# Sensor.net
KiCad netlist of a schematic drawn in Altium Designer
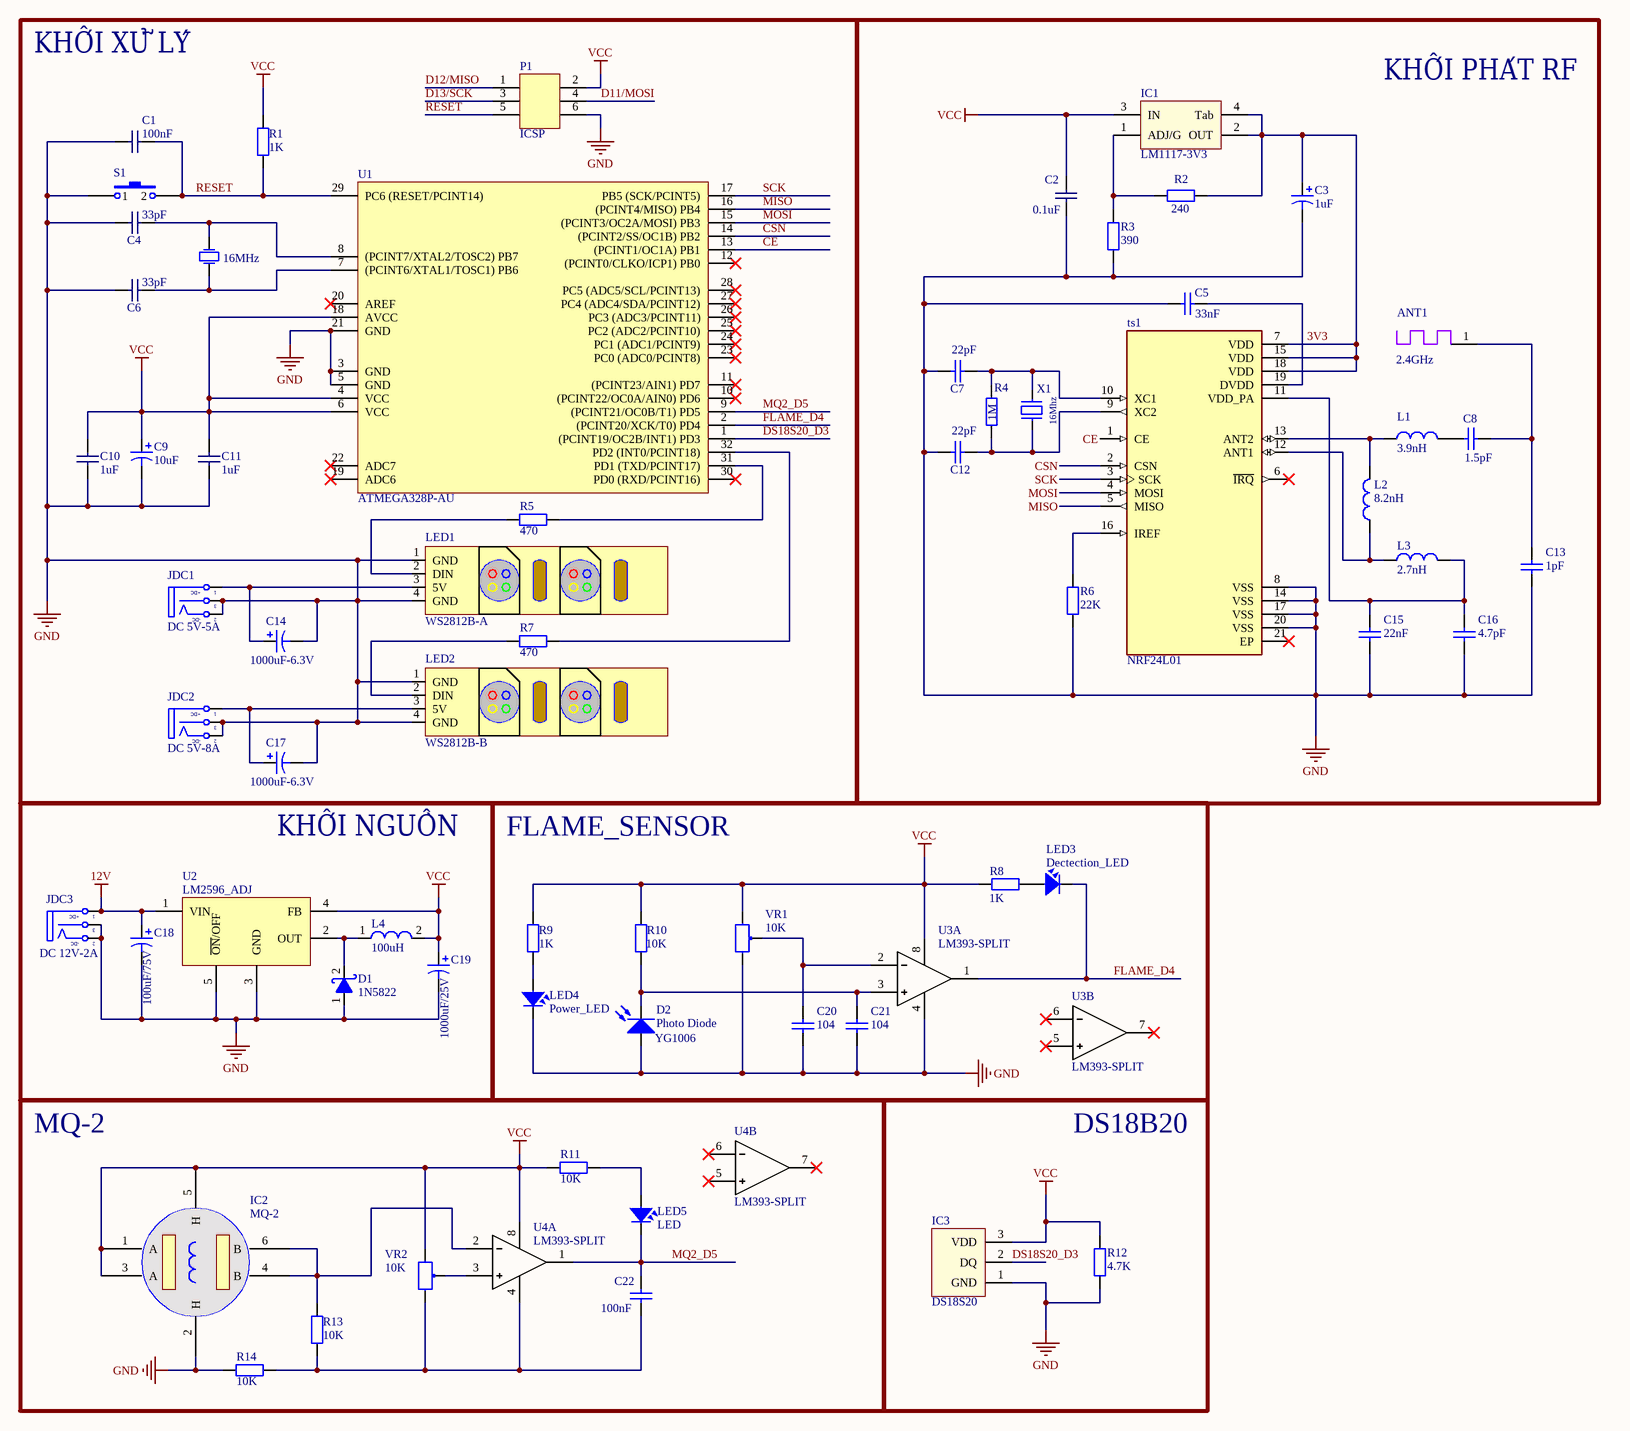
[diagram p0: Sensor.SchDoc]

(export (version "E")
  (design (tool "Eeschema 10.0.6"))
  (components
    (comp (ref "ANT1")
      (value "2.4GHz")
      (footprint "PATCH ANTEN 2.45GHZ")
      (description "PCB ANTENNA 2.45GHZ")
      (libsource (lib "BYTECH_HW_LIB_2019 (1)") (part "PCB antenna 2.45GHZ"))
    )
    (comp (ref "C1")
      (value "100nF")
      (footprint "thuvien_altium:CAP0603")
      (description "capacitor non polar")
      (libsource (lib "thuvien_altium") (part "capacitor_non_polar"))
    )
    (comp (ref "C2")
      (value "0.1uF")
      (footprint "thuvien_altium:CAPC0805")
      (description "capacitor non polar")
      (libsource (lib "thuvien_altium") (part "capacitor_non_polar"))
    )
    (comp (ref "C3")
      (value "1uF")
      (footprint "CAP_0805")
      (description "Polarized Capacitor (Axial)")
      (fields (field (name "PUBLISHER") "Altium Limited"))
      (libsource (lib "My Library") (part "Cap Pol 5mm"))
    )
    (comp (ref "C4")
      (value "33pF")
      (footprint "thuvien_altium:CAP0603")
      (description "capacitor non polar")
      (libsource (lib "thuvien_altium") (part "capacitor_non_polar"))
    )
    (comp (ref "C5")
      (value "33nF")
      (footprint "CAPC0805")
      (description "Capacitor")
      (fields (field (name "PUBLISHER") "Altium Limited"))
      (libsource (lib "My Library") (part "CapCeramic"))
    )
    (comp (ref "C6")
      (value "33pF")
      (footprint "thuvien_altium:CAP0603")
      (description "capacitor non polar")
      (libsource (lib "thuvien_altium") (part "capacitor_non_polar"))
    )
    (comp (ref "C7")
      (value "22pF")
      (footprint "CAPC0805")
      (description "Capacitor")
      (fields (field (name "PUBLISHER") "Altium Limited"))
      (libsource (lib "My Library") (part "CapCeramic"))
    )
    (comp (ref "C8")
      (value "1.5pF")
      (footprint "CAPC0805")
      (description "Capacitor")
      (fields (field (name "PUBLISHER") "Altium Limited"))
      (libsource (lib "My Library") (part "CapCeramic"))
    )
    (comp (ref "C9")
      (value "10uF")
      (footprint "thuvien_altium:CAP1206_TANTALUM_YELLOW")
      (description "CAP TANT 10UF 16V 10% 1206")
      (fields (field (name "TOLERANCE") "±10%"))
      (libsource (lib "thuvien_altium") (part "T491A106K016AT"))
    )
    (comp (ref "C10")
      (value "1uF")
      (footprint "thuvien_altium:CAP0603")
      (description "capacitor non polar")
      (libsource (lib "thuvien_altium") (part "capacitor_non_polar"))
    )
    (comp (ref "C11")
      (value "1uF")
      (footprint "thuvien_altium:CAP0603")
      (description "capacitor non polar")
      (libsource (lib "thuvien_altium") (part "capacitor_non_polar"))
    )
    (comp (ref "C12")
      (value "22pF")
      (footprint "CAPC0805")
      (description "Capacitor")
      (fields (field (name "PUBLISHER") "Altium Limited"))
      (libsource (lib "My Library") (part "CapCeramic"))
    )
    (comp (ref "C13")
      (value "1pF")
      (footprint "CAPC0805")
      (description "Capacitor")
      (fields (field (name "PUBLISHER") "Altium Limited"))
      (libsource (lib "My Library") (part "CapCeramic"))
    )
    (comp (ref "C14")
      (value "1000uF-6.3V")
      (footprint "CAP-ALU-SMD-J")
      (description "Polarized Capacitor (Axial)")
      (fields (field (name "PUBLISHER") "Altium Limited"))
      (libsource (lib "My Library") (part "Cap Pol 5mm"))
    )
    (comp (ref "C15")
      (value "22nF")
      (footprint "CAPC0805")
      (description "Capacitor")
      (fields (field (name "PUBLISHER") "Altium Limited"))
      (libsource (lib "My Library") (part "CapCeramic"))
    )
    (comp (ref "C16")
      (value "4.7pF")
      (footprint "CAPC0805")
      (description "Capacitor")
      (fields (field (name "PUBLISHER") "Altium Limited"))
      (libsource (lib "My Library") (part "CapCeramic"))
    )
    (comp (ref "C17")
      (value "1000uF-6.3V")
      (footprint "CAP-ALU-SMD-J")
      (description "Polarized Capacitor (Axial)")
      (fields (field (name "PUBLISHER") "Altium Limited"))
      (libsource (lib "My Library") (part "Cap Pol 5mm"))
    )
    (comp (ref "C18")
      (value "100uF/75V")
      (footprint "C5mm")
      (description "Polarized Capacitor (Axial)")
      (fields (field (name "PUBLISHER") "Altium Limited"))
      (libsource (lib "My Library") (part "Cap Pol 5mm"))
    )
    (comp (ref "C19")
      (value "1000uF/25V")
      (footprint "C5mm")
      (description "Polarized Capacitor (Axial)")
      (fields (field (name "PUBLISHER") "Altium Limited"))
      (libsource (lib "My Library") (part "Cap Pol 5mm"))
    )
    (comp (ref "C20")
      (value "104")
      (footprint "C0805")
      (description "Capacitor")
      (fields (field (name "PUBLISHER") "Altium Limited"))
      (libsource (lib "My Library") (part "CapSMD"))
    )
    (comp (ref "C21")
      (value "104")
      (footprint "C0805")
      (description "Capacitor")
      (fields (field (name "PUBLISHER") "Altium Limited"))
      (libsource (lib "My Library") (part "CapSMD"))
    )
    (comp (ref "C22")
      (value "100nF")
      (footprint "CAP_0805")
      (description "Capacitor")
      (fields (field (name "PUBLISHER") "Altium Limited"))
      (libsource (lib "My Library") (part "CapCeramic"))
    )
    (comp (ref "D1")
      (value "1N5822")
      (footprint "DIOAD3070W130L950D530")
      (description "Schottky Rectifiers")
      (libsource (lib "My Library") (part "1N5822"))
    )
    (comp (ref "D2")
      (value "Photo Diode")
      (footprint "LED-5 GRe")
      (description "Photosensitive Diode")
      (fields (field (name "YG1006") "YG1006"))
      (libsource (lib "My Library") (part "Photo Diode"))
    )
    (comp (ref "IC1")
      (value "LM1117-3V3")
      (footprint "SOT223-4N")
      (description "3v3")
      (libsource (lib "[Devzone.vn]_SchLibrary") (part "LM1117_1"))
    )
    (comp (ref "IC2")
      (value "MQ-2")
      (footprint "MQ-2")
      (description "MQ-2 GAS SENSOR")
      (libsource (lib "My Library") (part "MQ-2"))
    )
    (comp (ref "IC3")
      (value "DS18S20")
      (footprint "JP3-C1T")
      (description "High Precision  1-Wire® Digital Thermometer")
      (libsource (lib "TechMT.VN_Lib_Project v2") (part "DS18S20"))
    )
    (comp (ref "JDC1")
      (value "DC 5V-5A")
      (footprint "DC-IN")
      (description "Jac DC input")
      (libsource (lib "[Devzone.vn]_SchLibrary") (part "DCIN"))
    )
    (comp (ref "JDC2")
      (value "DC 5V-8A")
      (footprint "DC-IN")
      (description "Jac DC input")
      (libsource (lib "[Devzone.vn]_SchLibrary") (part "DCIN"))
    )
    (comp (ref "JDC3")
      (value "DC 12V-2A")
      (footprint "DC-IN")
      (description "Jac DC input")
      (libsource (lib "[Devzone.vn]_SchLibrary") (part "DCIN"))
    )
    (comp (ref "L1")
      (value "3.9nH")
      (footprint "INDC_DR127-1")
      (description "Inductor")
      (libsource (lib "My Library") (part "L1"))
    )
    (comp (ref "L2")
      (value "8.2nH")
      (footprint "INDC_DR127-1")
      (description "Inductor")
      (libsource (lib "My Library") (part "L1"))
    )
    (comp (ref "L3")
      (value "2.7nH")
      (footprint "INDC_DR127-1")
      (description "Inductor")
      (libsource (lib "My Library") (part "L1"))
    )
    (comp (ref "L4")
      (value "100uH")
      (footprint "Inductor_SMD")
      (description "Inductor")
      (libsource (lib "My Library") (part "Inductor"))
    )
    (comp (ref "LED1")
      (value "WS2812B-A")
      (footprint "WS2812B")
      (description "WS2812B")
      (libsource (lib "CamBien") (part "WS2812B"))
    )
    (comp (ref "LED2")
      (value "WS2812B-B")
      (footprint "WS2812B")
      (description "WS2812B")
      (libsource (lib "CamBien") (part "WS2812B"))
    )
    (comp (ref "LED3")
      (value "Dectection_LED")
      (footprint "LED-0805-Blue")
      (libsource (lib "My Library") (part "LED SMD"))
    )
    (comp (ref "LED4")
      (value "Power_LED")
      (footprint "LED-0805-Red")
      (libsource (lib "My Library") (part "LED SMD"))
    )
    (comp (ref "LED5")
      (value "LED")
      (footprint "LED-0805-Red")
      (description "LED Single colour Green and Red")
      (libsource (lib "My Library") (part "LED"))
    )
    (comp (ref "P1")
      (value "ICSP")
      (footprint "thuvien_altium:HDR_M_2X3_2.54")
      (libsource (lib "thuvien_altium") (part "header_2x3pins"))
    )
    (comp (ref "R1")
      (value "1K")
      (footprint "DIEN TRO 0805")
      (description "Resistor SMD 0805")
      (fields (field (name "PUBLISHER") "Altium Limited"))
      (libsource (lib "") (part "R0805_1"))
    )
    (comp (ref "R2")
      (value "240")
      (footprint "RES_SMD_0805")
      (description "Resistor 1/4W")
      (libsource (lib "My Library") (part "R1/4W"))
    )
    (comp (ref "R3")
      (value "390")
      (footprint "RES_SMD_0805")
      (description "Resistor 1/4W")
      (libsource (lib "My Library") (part "R1/4W"))
    )
    (comp (ref "R4")
      (value "1M")
      (footprint "RES_SMD_0805")
      (description "Resistor 1/4W")
      (libsource (lib "My Library") (part "R1/4W"))
    )
    (comp (ref "R5")
      (value "470")
      (footprint "DIEN TRO 0805")
      (description "Resistor SMD 0805")
      (fields (field (name "PUBLISHER") "Altium Limited"))
      (libsource (lib "My Library") (part "R0805"))
    )
    (comp (ref "R6")
      (value "22K")
      (footprint "RES_SMD_0805")
      (description "Resistor 1/4W")
      (libsource (lib "My Library") (part "R1/4W"))
    )
    (comp (ref "R7")
      (value "470")
      (footprint "DIEN TRO 0805")
      (description "Resistor SMD 0805")
      (fields (field (name "PUBLISHER") "Altium Limited"))
      (libsource (lib "My Library") (part "R0805"))
    )
    (comp (ref "R8")
      (value "1K")
      (footprint "DIEN TRO 0805")
      (description "Resistor SMD 0805")
      (fields (field (name "PUBLISHER") "Altium Limited"))
      (libsource (lib "My Library") (part "R0805"))
    )
    (comp (ref "R9")
      (value "1K")
      (footprint "DIEN TRO 0805")
      (description "Resistor SMD 0805")
      (fields (field (name "Comment") "R0805") (field (name "PUBLISHER") "Altium Limited"))
      (libsource (lib "") (part "R0805_2"))
    )
    (comp (ref "R10")
      (value "10K")
      (footprint "DIEN TRO 0805")
      (description "Resistor SMD 0805")
      (fields (field (name "PUBLISHER") "Altium Limited"))
      (libsource (lib "") (part "R0805_2"))
    )
    (comp (ref "R11")
      (value "10K")
      (footprint "DIEN TRO 0805")
      (description "Resistor SMD 0805")
      (fields (field (name "PUBLISHER") "Altium Limited"))
      (libsource (lib "My Library") (part "R0805"))
    )
    (comp (ref "R12")
      (value "4.7K")
      (footprint "RES-SMD-0805")
      (description "Resistor 1/4W")
      (libsource (lib "My Library") (part "R1/4W"))
    )
    (comp (ref "R13")
      (value "10K")
      (footprint "DIEN TRO 0805")
      (description "Resistor SMD 0805")
      (fields (field (name "PUBLISHER") "Altium Limited"))
      (libsource (lib "") (part "R0805_1"))
    )
    (comp (ref "R14")
      (value "10K")
      (footprint "DIEN TRO 0805")
      (description "Resistor SMD 0805")
      (fields (field (name "PUBLISHER") "Altium Limited"))
      (libsource (lib "My Library") (part "R0805"))
    )
    (comp (ref "S1")
      (value "RESET")
      (footprint "thuvien_altium:SW_B3U-1000P")
      (description "Switch")
      (fields (field (name "PUBLISHER") "Altium Limited"))
      (libsource (lib "thuvien_altium") (part "SW-PB-2pin"))
    )
    (comp (ref "ts1")
      (value "NRF24L01")
      (footprint "QFN50P400X400X95-21N")
      (description "IC RF TxRx Only General ISM > 1GHZ 2.4GHz 20-VFQFN Exposed Pad")
      (fields (field (name "MP") "NRF24L01+") (field (name "MF") "Nordic Semiconductor"))
      (libsource (lib "NRF24L01-SE") (part "NRF24L01"))
    )
    (comp (ref "U1")
      (value "ATMEGA328P-AU")
      (footprint "thuvien_altium:TQFP-32")
      (description "AVR AVR® ATmega Microcontroller IC 8-Bit 20MHz 32KB (16K x 16) FLASH 32-TQFP (7x7)")
      (libsource (lib "thuvien_altium") (part "atmega328p-au"))
    )
    (comp (ref "U2")
      (value "LM2596_ADJ")
      (footprint "thuvien_altium:TO263-5")
      (libsource (lib "thuvien_altium") (part "LM2596_ADJ"))
    )
    (comp (ref "U3")
      (value "LM393-SPLIT")
      (footprint "SO8")
      (description "IC DUAL COMPARATOR")
      (libsource (lib "My Library") (part "LM393-SPLIT"))
    )
    (comp (ref "U4")
      (value "LM393-SPLIT")
      (footprint "SO8")
      (description "IC DUAL COMPARATOR")
      (libsource (lib "My Library") (part "LM393-SPLIT"))
    )
    (comp (ref "VR1")
      (value "10K")
      (footprint "VR1")
      (description "Var Resistor")
      (libsource (lib "My Library") (part "VR"))
    )
    (comp (ref "VR2")
      (value "10K")
      (footprint "VR1")
      (description "Var Resistor")
      (libsource (lib "My Library") (part "VR"))
    )
    (comp (ref "X1")
      (value "16Mhz")
      (footprint "XTAL_SMD_HC-49S")
      (description "Crystal For all Crystal 2pin.")
      (libsource (lib "My Library") (part "XT2"))
    )
    (comp (ref "Y1")
      (value "16MHz")
      (footprint "XTAL_SMD_HC-49S")
      (description "Crystal Oscillator")
      (fields (field (name "PUBLISHER") "Altium Limited"))
      (libsource (lib "My Library") (part "XTAL"))
    )
  )
  (nets
    (net (code "1") (name "/3V3") (class "Default")
      (node (ref "C3") (pin "1") (pinfunction "1_1") (pintype "passive"))
      (node (ref "IC1") (pin "2") (pinfunction "OUT_2") (pintype "passive"))
      (node (ref "IC1") (pin "4") (pinfunction "Tab_4") (pintype "passive"))
      (node (ref "R2") (pin "1") (pinfunction "1_1") (pintype "passive"))
      (node (ref "ts1") (pin "15") (pinfunction "VDD_15") (pintype "power_in"))
      (node (ref "ts1") (pin "18") (pinfunction "VDD_18") (pintype "power_in"))
      (node (ref "ts1") (pin "7") (pinfunction "VDD_7") (pintype "power_in"))
    )
    (net (code "2") (name "/CE") (class "Default")
      (node (ref "U1") (pin "13") (pinfunction "(PCINT1/OC1A)_PB1_13") (pintype "power_in"))
      (node (ref "ts1") (pin "1") (pinfunction "CE_1") (pintype "input"))
    )
    (net (code "3") (name "/CSN") (class "Default")
      (node (ref "U1") (pin "14") (pinfunction "(PCINT2/SS/OC1B)_PB2_14") (pintype "power_in"))
      (node (ref "ts1") (pin "2") (pinfunction "CSN_2") (pintype "input"))
    )
    (net (code "4") (name "/D11{slash}MOSI") (class "Default")
      (node (ref "P1") (pin "4") (pinfunction "4_4") (pintype "power_in"))
    )
    (net (code "5") (name "/D12{slash}MISO") (class "Default")
      (node (ref "P1") (pin "1") (pinfunction "1_1") (pintype "power_in"))
    )
    (net (code "6") (name "/D13{slash}SCK") (class "Default")
      (node (ref "P1") (pin "3") (pinfunction "3_3") (pintype "power_in"))
    )
    (net (code "7") (name "/DS18S20_D3") (class "Default")
      (node (ref "IC3") (pin "2") (pinfunction "DQ_2") (pintype "passive"))
      (node (ref "U1") (pin "1") (pinfunction "(PCINT19/OC2B/INT1)_PD3_1") (pintype "power_in"))
    )
    (net (code "8") (name "/FLAME_D4") (class "Default")
      (node (ref "LED3") (pin "2") (pinfunction "2_2") (pintype "passive"))
      (node (ref "U1") (pin "2") (pinfunction "(PCINT20/XCK/T0)_PD4_2") (pintype "power_in"))
      (node (ref "U3") (pin "1") (pintype "passive"))
    )
    (net (code "9") (name "/MISO") (class "Default")
      (node (ref "U1") (pin "16") (pinfunction "(PCINT4/MISO)_PB4_16") (pintype "power_in"))
      (node (ref "ts1") (pin "5") (pinfunction "MISO_5") (pintype "output"))
    )
    (net (code "10") (name "/MOSI") (class "Default")
      (node (ref "U1") (pin "15") (pinfunction "(PCINT3/OC2A/MOSI)_PB3_15") (pintype "power_in"))
      (node (ref "ts1") (pin "4") (pinfunction "MOSI_4") (pintype "input"))
    )
    (net (code "11") (name "/MQ2_D5") (class "Default")
      (node (ref "C22") (pin "2") (pinfunction "2_2") (pintype "passive"))
      (node (ref "LED5") (pin "2") (pinfunction "2_2") (pintype "passive"))
      (node (ref "U1") (pin "9") (pinfunction "(PCINT21/OC0B/T1)_PD5_9") (pintype "power_in"))
      (node (ref "U4") (pin "1") (pintype "passive"))
    )
    (net (code "12") (name "/RESET") (class "Default")
      (node (ref "C1") (pin "2") (pinfunction "2_2") (pintype "power_in"))
      (node (ref "P1") (pin "5") (pinfunction "5_5") (pintype "power_in"))
      (node (ref "R1") (pin "2") (pinfunction "2_2") (pintype "passive"))
      (node (ref "S1") (pin "2") (pinfunction "2_2") (pintype "passive"))
      (node (ref "U1") (pin "29") (pinfunction "PC6_(RESET/PCINT14)_29") (pintype "power_in"))
    )
    (net (code "13") (name "/SCK") (class "Default")
      (node (ref "U1") (pin "17") (pinfunction "PB5_(SCK/PCINT5)_17") (pintype "power_in"))
      (node (ref "ts1") (pin "3") (pinfunction "SCK_3") (pintype "input"))
    )
    (net (code "14") (name "12V") (class "Default")
      (node (ref "C18") (pin "1") (pinfunction "1_1") (pintype "passive"))
      (node (ref "JDC3") (pin "1") (pinfunction "T_1") (pintype "passive"))
      (node (ref "U2") (pin "1") (pinfunction "VIN_1") (pintype "power_in"))
    )
    (net (code "15") (name "GND") (class "Default")
      (node (ref "C1") (pin "1") (pinfunction "1_1") (pintype "power_in"))
      (node (ref "C10") (pin "2") (pinfunction "2_2") (pintype "power_in"))
      (node (ref "C11") (pin "2") (pinfunction "2_2") (pintype "power_in"))
      (node (ref "C12") (pin "1") (pinfunction "1_1") (pintype "passive"))
      (node (ref "C13") (pin "1") (pinfunction "1_1") (pintype "passive"))
      (node (ref "C14") (pin "2") (pinfunction "2_2") (pintype "passive"))
      (node (ref "C15") (pin "1") (pinfunction "1_1") (pintype "passive"))
      (node (ref "C16") (pin "1") (pinfunction "1_1") (pintype "passive"))
      (node (ref "C17") (pin "2") (pinfunction "2_2") (pintype "passive"))
      (node (ref "C18") (pin "2") (pinfunction "2_2") (pintype "passive"))
      (node (ref "C19") (pin "2") (pinfunction "2_2") (pintype "passive"))
      (node (ref "C2") (pin "1") (pinfunction "1_1") (pintype "power_in"))
      (node (ref "C20") (pin "1") (pinfunction "1_1") (pintype "passive"))
      (node (ref "C21") (pin "1") (pinfunction "1_1") (pintype "passive"))
      (node (ref "C3") (pin "2") (pinfunction "2_2") (pintype "passive"))
      (node (ref "C4") (pin "1") (pinfunction "1_1") (pintype "power_in"))
      (node (ref "C5") (pin "1") (pinfunction "1_1") (pintype "passive"))
      (node (ref "C6") (pin "1") (pinfunction "1_1") (pintype "power_in"))
      (node (ref "C7") (pin "1") (pinfunction "1_1") (pintype "passive"))
      (node (ref "C9") (pin "2") (pinfunction "2_2") (pintype "passive"))
      (node (ref "D1") (pin "1") (pinfunction "A_1") (pintype "passive"))
      (node (ref "D2") (pin "1") (pinfunction "A_1") (pintype "passive"))
      (node (ref "IC2") (pin "2") (pinfunction "H_2") (pintype "passive"))
      (node (ref "IC3") (pin "1") (pinfunction "GND_1") (pintype "passive"))
      (node (ref "JDC1") (pin "2") (pinfunction "TN_2") (pintype "passive"))
      (node (ref "JDC1") (pin "3") (pinfunction "S_3") (pintype "power_in"))
      (node (ref "JDC2") (pin "2") (pinfunction "TN_2") (pintype "passive"))
      (node (ref "JDC2") (pin "3") (pinfunction "S_3") (pintype "power_in"))
      (node (ref "JDC3") (pin "2") (pinfunction "TN_2") (pintype "passive"))
      (node (ref "JDC3") (pin "3") (pinfunction "S_3") (pintype "power_in"))
      (node (ref "LED1") (pin "1") (pinfunction "GND_1") (pintype "passive"))
      (node (ref "LED1") (pin "4") (pinfunction "GND_4") (pintype "passive"))
      (node (ref "LED2") (pin "1") (pinfunction "GND_1") (pintype "passive"))
      (node (ref "LED2") (pin "4") (pinfunction "GND_4") (pintype "passive"))
      (node (ref "LED4") (pin "2") (pinfunction "2_2") (pintype "passive"))
      (node (ref "P1") (pin "6") (pinfunction "6_6") (pintype "power_in"))
      (node (ref "R12") (pin "1") (pinfunction "1_1") (pintype "passive"))
      (node (ref "R14") (pin "2") (pinfunction "2_2") (pintype "passive"))
      (node (ref "R3") (pin "1") (pinfunction "1_1") (pintype "passive"))
      (node (ref "R6") (pin "1") (pinfunction "1_1") (pintype "passive"))
      (node (ref "S1") (pin "1") (pinfunction "1_1") (pintype "passive"))
      (node (ref "U1") (pin "21") (pinfunction "GND_21") (pintype "power_in"))
      (node (ref "U1") (pin "3") (pinfunction "GND_3") (pintype "power_in"))
      (node (ref "U1") (pin "5") (pinfunction "GND_5") (pintype "power_in"))
      (node (ref "U2") (pin "3") (pinfunction "GND_3") (pintype "power_in"))
      (node (ref "U2") (pin "5") (pinfunction "~{ON}/OFF_5") (pintype "power_in"))
      (node (ref "U3") (pin "4") (pinfunction "Vcc-_4") (pintype "passive"))
      (node (ref "VR1") (pin "3") (pinfunction "3_3") (pintype "passive"))
      (node (ref "ts1") (pin "14") (pinfunction "VSS_14") (pintype "power_in"))
      (node (ref "ts1") (pin "17") (pinfunction "VSS_17") (pintype "power_in"))
      (node (ref "ts1") (pin "20") (pinfunction "VSS_20") (pintype "power_in"))
      (node (ref "ts1") (pin "8") (pinfunction "VSS_8") (pintype "power_in"))
    )
    (net (code "16") (name "Net-(ANT1-ANT)") (class "Default")
      (node (ref "ANT1") (pin "1") (pinfunction "ANT_1") (pintype "passive"))
      (node (ref "C13") (pin "2") (pinfunction "2_2") (pintype "passive"))
      (node (ref "C8") (pin "2") (pinfunction "2_2") (pintype "passive"))
    )
    (net (code "17") (name "Net-(C8-Pad1)") (class "Default")
      (node (ref "C8") (pin "1") (pinfunction "1_1") (pintype "passive"))
      (node (ref "L1") (pin "2") (pinfunction "2_2") (pintype "passive"))
    )
    (net (code "18") (name "Net-(C20-Pad2)") (class "Default")
      (node (ref "C20") (pin "2") (pinfunction "2_2") (pintype "passive"))
      (node (ref "U3") (pin "2") (pintype "passive"))
      (node (ref "VR1") (pin "2") (pinfunction "2_2") (pintype "passive"))
    )
    (net (code "19") (name "Net-(D1-K)") (class "Default")
      (node (ref "D1") (pin "2") (pinfunction "K_2") (pintype "passive"))
      (node (ref "L4") (pin "1") (pinfunction "1_1") (pintype "passive"))
      (node (ref "U2") (pin "2") (pinfunction "OUT_2") (pintype "power_in"))
    )
    (net (code "20") (name "Net-(D2-K)") (class "Default")
      (node (ref "C21") (pin "2") (pinfunction "2_2") (pintype "passive"))
      (node (ref "D2") (pin "2") (pinfunction "K_2") (pintype "passive"))
      (node (ref "R10") (pin "1") (pinfunction "1_1") (pintype "passive"))
      (node (ref "U3") (pin "3") (pintype "passive"))
    )
    (net (code "21") (name "Net-(IC1-ADJ{slash}G)") (class "Default")
      (node (ref "IC1") (pin "1") (pinfunction "ADJ/G_1") (pintype "passive"))
      (node (ref "R2") (pin "2") (pinfunction "2_2") (pintype "passive"))
      (node (ref "R3") (pin "2") (pinfunction "2_2") (pintype "passive"))
    )
    (net (code "22") (name "Net-(IC2-B-Pad4)") (class "Default")
      (node (ref "IC2") (pin "4") (pinfunction "B_4") (pintype "passive"))
      (node (ref "IC2") (pin "6") (pinfunction "B_6") (pintype "passive"))
      (node (ref "R13") (pin "1") (pinfunction "1_1") (pintype "passive"))
      (node (ref "U4") (pin "2") (pintype "passive"))
    )
    (net (code "23") (name "Net-(JDC1-T)") (class "Default")
      (node (ref "C14") (pin "1") (pinfunction "1_1") (pintype "passive"))
      (node (ref "JDC1") (pin "1") (pinfunction "T_1") (pintype "passive"))
      (node (ref "LED1") (pin "3") (pinfunction "5V_3") (pintype "passive"))
    )
    (net (code "24") (name "Net-(JDC2-T)") (class "Default")
      (node (ref "C17") (pin "1") (pinfunction "1_1") (pintype "passive"))
      (node (ref "JDC2") (pin "1") (pinfunction "T_1") (pintype "passive"))
      (node (ref "LED2") (pin "3") (pinfunction "5V_3") (pintype "passive"))
    )
    (net (code "25") (name "Net-(LED1-DIN)") (class "Default")
      (node (ref "LED1") (pin "2") (pinfunction "DIN_2") (pintype "passive"))
      (node (ref "R5") (pin "2") (pinfunction "2_2") (pintype "passive"))
    )
    (net (code "26") (name "Net-(LED2-DIN)") (class "Default")
      (node (ref "LED2") (pin "2") (pinfunction "DIN_2") (pintype "passive"))
      (node (ref "R7") (pin "2") (pinfunction "2_2") (pintype "passive"))
    )
    (net (code "27") (name "Net-(LED3-Pad1)") (class "Default")
      (node (ref "LED3") (pin "1") (pinfunction "1_1") (pintype "passive"))
      (node (ref "R8") (pin "1") (pinfunction "1_1") (pintype "passive"))
    )
    (net (code "28") (name "Net-(LED4-Pad1)") (class "Default")
      (node (ref "LED4") (pin "1") (pinfunction "1_1") (pintype "passive"))
      (node (ref "R9") (pin "1") (pinfunction "1_1") (pintype "passive"))
    )
    (net (code "29") (name "Net-(LED5-Pad1)") (class "Default")
      (node (ref "LED5") (pin "1") (pinfunction "1_1") (pintype "passive"))
      (node (ref "R11") (pin "1") (pinfunction "1_1") (pintype "passive"))
    )
    (net (code "30") (name "Net-(U1-(PCINT6{slash}XTAL1{slash}TOSC1)_PB6)") (class "Default")
      (node (ref "C6") (pin "2") (pinfunction "2_2") (pintype "power_in"))
      (node (ref "U1") (pin "7") (pinfunction "(PCINT6/XTAL1/TOSC1)_PB6_7") (pintype "power_in"))
      (node (ref "Y1") (pin "1") (pinfunction "OSC1_1") (pintype "passive"))
    )
    (net (code "31") (name "Net-(U1-(PCINT7{slash}XTAL2{slash}TOSC2)_PB7)") (class "Default")
      (node (ref "C4") (pin "2") (pinfunction "2_2") (pintype "power_in"))
      (node (ref "U1") (pin "8") (pinfunction "(PCINT7/XTAL2/TOSC2)_PB7_8") (pintype "power_in"))
      (node (ref "Y1") (pin "2") (pinfunction "OSC2_2") (pintype "passive"))
    )
    (net (code "32") (name "Net-(U1-PD1_(TXD{slash}PCINT17))") (class "Default")
      (node (ref "R5") (pin "1") (pinfunction "1_1") (pintype "passive"))
      (node (ref "U1") (pin "31") (pinfunction "PD1_(TXD/PCINT17)_31") (pintype "power_in"))
    )
    (net (code "33") (name "Net-(U1-PD2_(INT0{slash}PCINT18))") (class "Default")
      (node (ref "R7") (pin "1") (pinfunction "1_1") (pintype "passive"))
      (node (ref "U1") (pin "32") (pinfunction "PD2_(INT0/PCINT18)_32") (pintype "power_in"))
    )
    (net (code "34") (name "Net-(U4-Pad3)") (class "Default")
      (node (ref "U4") (pin "3") (pintype "passive"))
      (node (ref "VR2") (pin "2") (pinfunction "2_2") (pintype "passive"))
    )
    (net (code "35") (name "Net-(U4A-Vcc-)") (class "Default")
      (node (ref "C22") (pin "1") (pinfunction "1_1") (pintype "passive"))
      (node (ref "R13") (pin "2") (pinfunction "2_2") (pintype "passive"))
      (node (ref "R14") (pin "1") (pinfunction "1_1") (pintype "passive"))
      (node (ref "U4") (pin "4") (pinfunction "Vcc-_4") (pintype "passive"))
      (node (ref "VR2") (pin "3") (pinfunction "3_3") (pintype "passive"))
    )
    (net (code "36") (name "Net-(ts1-ANT1)") (class "Default")
      (node (ref "L2") (pin "1") (pinfunction "1_1") (pintype "passive"))
      (node (ref "L3") (pin "1") (pinfunction "1_1") (pintype "passive"))
      (node (ref "ts1") (pin "12") (pinfunction "ANT1_12") (pintype "bidirectional"))
    )
    (net (code "37") (name "Net-(ts1-ANT2)") (class "Default")
      (node (ref "L1") (pin "1") (pinfunction "1_1") (pintype "passive"))
      (node (ref "L2") (pin "2") (pinfunction "2_2") (pintype "passive"))
      (node (ref "ts1") (pin "13") (pinfunction "ANT2_13") (pintype "bidirectional"))
    )
    (net (code "38") (name "Net-(ts1-DVDD)") (class "Default")
      (node (ref "C5") (pin "2") (pinfunction "2_2") (pintype "passive"))
      (node (ref "ts1") (pin "19") (pinfunction "DVDD_19") (pintype "power_in"))
    )
    (net (code "39") (name "Net-(ts1-IREF)") (class "Default")
      (node (ref "R6") (pin "2") (pinfunction "2_2") (pintype "passive"))
      (node (ref "ts1") (pin "16") (pinfunction "IREF_16") (pintype "input"))
    )
    (net (code "40") (name "Net-(ts1-VDD_PA)") (class "Default")
      (node (ref "C15") (pin "2") (pinfunction "2_2") (pintype "passive"))
      (node (ref "C16") (pin "2") (pinfunction "2_2") (pintype "passive"))
      (node (ref "L3") (pin "2") (pinfunction "2_2") (pintype "passive"))
      (node (ref "ts1") (pin "11") (pinfunction "VDD_PA_11") (pintype "power_in"))
    )
    (net (code "41") (name "Net-(ts1-XC1)") (class "Default")
      (node (ref "C7") (pin "2") (pinfunction "2_2") (pintype "passive"))
      (node (ref "R4") (pin "2") (pinfunction "2_2") (pintype "passive"))
      (node (ref "X1") (pin "1") (pinfunction "1_1") (pintype "passive"))
      (node (ref "ts1") (pin "10") (pinfunction "XC1_10") (pintype "input"))
    )
    (net (code "42") (name "Net-(ts1-XC2)") (class "Default")
      (node (ref "C12") (pin "2") (pinfunction "2_2") (pintype "passive"))
      (node (ref "R4") (pin "1") (pinfunction "1_1") (pintype "passive"))
      (node (ref "X1") (pin "2") (pinfunction "2_2") (pintype "passive"))
      (node (ref "ts1") (pin "9") (pinfunction "XC2_9") (pintype "output"))
    )
    (net (code "43") (name "VCC") (class "Default")
      (node (ref "C10") (pin "1") (pinfunction "1_1") (pintype "power_in"))
      (node (ref "C11") (pin "1") (pinfunction "1_1") (pintype "power_in"))
      (node (ref "C19") (pin "1") (pinfunction "1_1") (pintype "passive"))
      (node (ref "C2") (pin "2") (pinfunction "2_2") (pintype "power_in"))
      (node (ref "C9") (pin "1") (pinfunction "1_1") (pintype "passive"))
      (node (ref "IC1") (pin "3") (pinfunction "IN_3") (pintype "passive"))
      (node (ref "IC2") (pin "1") (pinfunction "A_1") (pintype "passive"))
      (node (ref "IC2") (pin "3") (pinfunction "A_3") (pintype "passive"))
      (node (ref "IC2") (pin "5") (pinfunction "H_5") (pintype "passive"))
      (node (ref "IC3") (pin "3") (pinfunction "VDD_3") (pintype "passive"))
      (node (ref "L4") (pin "2") (pinfunction "2_2") (pintype "passive"))
      (node (ref "P1") (pin "2") (pinfunction "2_2") (pintype "power_in"))
      (node (ref "R1") (pin "1") (pinfunction "1_1") (pintype "passive"))
      (node (ref "R10") (pin "2") (pinfunction "2_2") (pintype "passive"))
      (node (ref "R11") (pin "2") (pinfunction "2_2") (pintype "passive"))
      (node (ref "R12") (pin "2") (pinfunction "2_2") (pintype "passive"))
      (node (ref "R8") (pin "2") (pinfunction "2_2") (pintype "passive"))
      (node (ref "R9") (pin "2") (pinfunction "2_2") (pintype "passive"))
      (node (ref "U1") (pin "18") (pinfunction "AVCC_18") (pintype "power_in"))
      (node (ref "U1") (pin "4") (pinfunction "VCC_4") (pintype "power_in"))
      (node (ref "U1") (pin "6") (pinfunction "VCC_6") (pintype "power_in"))
      (node (ref "U2") (pin "4") (pinfunction "FB_4") (pintype "power_in"))
      (node (ref "U3") (pin "8") (pinfunction "Vcc+_8") (pintype "passive"))
      (node (ref "U4") (pin "8") (pinfunction "Vcc+_8") (pintype "passive"))
      (node (ref "VR1") (pin "1") (pinfunction "1_1") (pintype "passive"))
      (node (ref "VR2") (pin "1") (pinfunction "1_1") (pintype "passive"))
    )
    (net (code "44") (name "unconnected-(U1-(PCINT0{slash}CLKO{slash}ICP1)_PB0-Pad12)") (class "Default")
      (node (ref "U1") (pin "12") (pinfunction "(PCINT0/CLKO/ICP1)_PB0_12") (pintype "power_in+no_connect"))
    )
    (net (code "45") (name "unconnected-(U1-(PCINT22{slash}OC0A{slash}AIN0)_PD6-Pad10)") (class "Default")
      (node (ref "U1") (pin "10") (pinfunction "(PCINT22/OC0A/AIN0)_PD6_10") (pintype "power_in+no_connect"))
    )
    (net (code "46") (name "unconnected-(U1-(PCINT23{slash}AIN1)_PD7-Pad11)") (class "Default")
      (node (ref "U1") (pin "11") (pinfunction "(PCINT23/AIN1)_PD7_11") (pintype "power_in+no_connect"))
    )
    (net (code "47") (name "unconnected-(U1-ADC6-Pad19)") (class "Default")
      (node (ref "U1") (pin "19") (pinfunction "ADC6_19") (pintype "power_in+no_connect"))
    )
    (net (code "48") (name "unconnected-(U1-ADC7-Pad22)") (class "Default")
      (node (ref "U1") (pin "22") (pinfunction "ADC7_22") (pintype "power_in+no_connect"))
    )
    (net (code "49") (name "unconnected-(U1-AREF-Pad20)") (class "Default")
      (node (ref "U1") (pin "20") (pinfunction "AREF_20") (pintype "power_in+no_connect"))
    )
    (net (code "50") (name "unconnected-(U1-PC0_(ADC0{slash}PCINT8)-Pad23)") (class "Default")
      (node (ref "U1") (pin "23") (pinfunction "PC0_(ADC0/PCINT8)_23") (pintype "power_in+no_connect"))
    )
    (net (code "51") (name "unconnected-(U1-PC1_(ADC1{slash}PCINT9)-Pad24)") (class "Default")
      (node (ref "U1") (pin "24") (pinfunction "PC1_(ADC1/PCINT9)_24") (pintype "power_in+no_connect"))
    )
    (net (code "52") (name "unconnected-(U1-PC2_(ADC2{slash}PCINT10)-Pad25)") (class "Default")
      (node (ref "U1") (pin "25") (pinfunction "PC2_(ADC2/PCINT10)_25") (pintype "power_in+no_connect"))
    )
    (net (code "53") (name "unconnected-(U1-PC3_(ADC3{slash}PCINT11)-Pad26)") (class "Default")
      (node (ref "U1") (pin "26") (pinfunction "PC3_(ADC3/PCINT11)_26") (pintype "power_in+no_connect"))
    )
    (net (code "54") (name "unconnected-(U1-PC4_(ADC4{slash}SDA{slash}PCINT12)-Pad27)") (class "Default")
      (node (ref "U1") (pin "27") (pinfunction "PC4_(ADC4/SDA/PCINT12)_27") (pintype "power_in+no_connect"))
    )
    (net (code "55") (name "unconnected-(U1-PC5_(ADC5{slash}SCL{slash}PCINT13)-Pad28)") (class "Default")
      (node (ref "U1") (pin "28") (pinfunction "PC5_(ADC5/SCL/PCINT13)_28") (pintype "power_in+no_connect"))
    )
    (net (code "56") (name "unconnected-(U1-PD0_(RXD{slash}PCINT16)-Pad30)") (class "Default")
      (node (ref "U1") (pin "30") (pinfunction "PD0_(RXD/PCINT16)_30") (pintype "power_in+no_connect"))
    )
    (net (code "57") (name "unconnected-(U3-Pad5)") (class "Default")
      (node (ref "U3") (pin "5") (pintype "passive+no_connect"))
    )
    (net (code "58") (name "unconnected-(U3-Pad6)") (class "Default")
      (node (ref "U3") (pin "6") (pintype "passive+no_connect"))
    )
    (net (code "59") (name "unconnected-(U3-Pad7)") (class "Default")
      (node (ref "U3") (pin "7") (pintype "passive+no_connect"))
    )
    (net (code "60") (name "unconnected-(U4-Pad5)") (class "Default")
      (node (ref "U4") (pin "5") (pintype "passive+no_connect"))
    )
    (net (code "61") (name "unconnected-(U4-Pad6)") (class "Default")
      (node (ref "U4") (pin "6") (pintype "passive+no_connect"))
    )
    (net (code "62") (name "unconnected-(U4-Pad7)") (class "Default")
      (node (ref "U4") (pin "7") (pintype "passive+no_connect"))
    )
    (net (code "63") (name "unconnected-(ts1-EP-Pad21)") (class "Default")
      (node (ref "ts1") (pin "21") (pinfunction "EP_21") (pintype "power_in+no_connect"))
    )
    (net (code "64") (name "unconnected-(ts1-~{IRQ}-Pad6)") (class "Default")
      (node (ref "ts1") (pin "6") (pinfunction "~{IRQ}_6") (pintype "output+no_connect"))
    )
  )
)
